# 2LCI2C.net
KiCad netlist of a schematic drawn in EAGLE
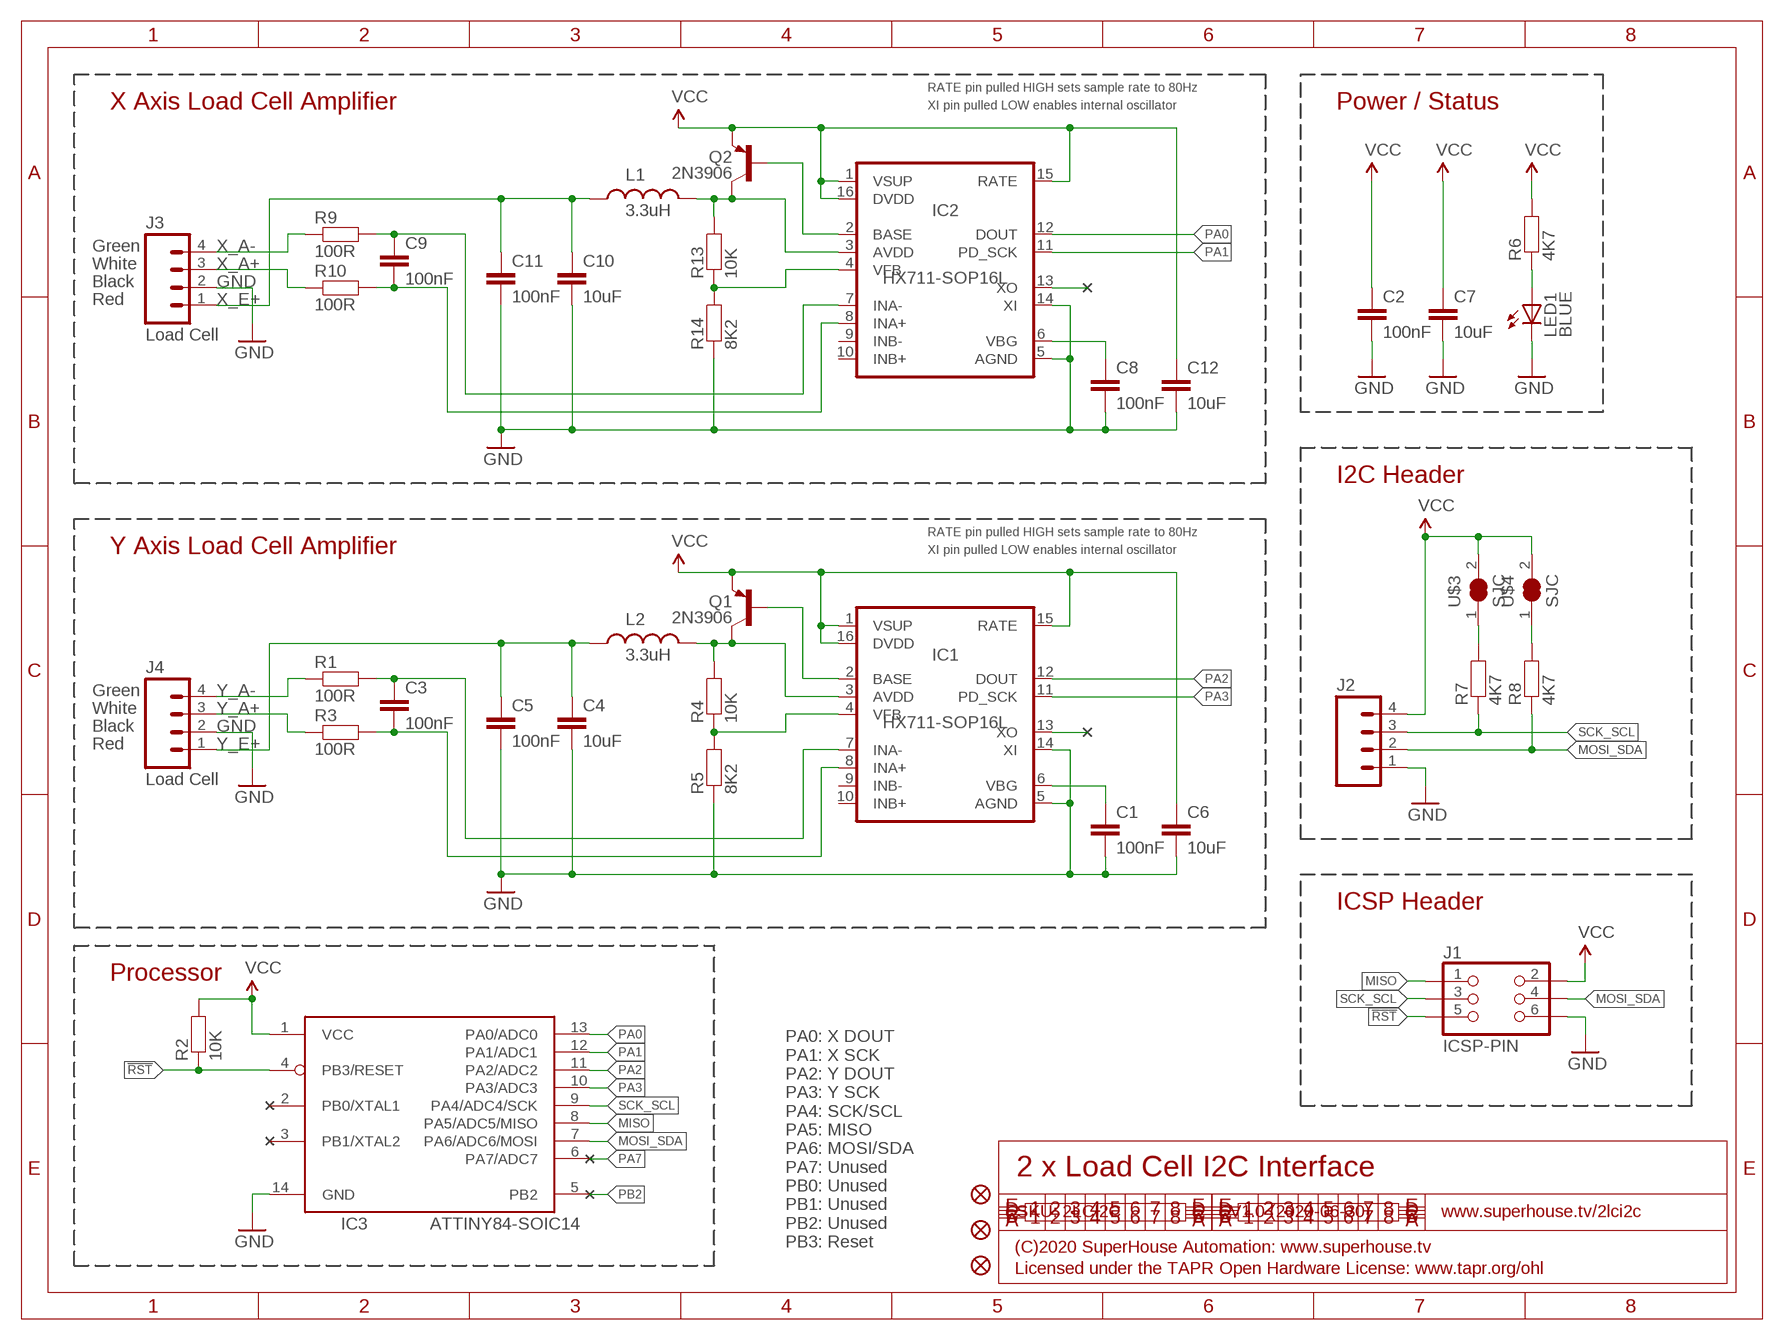
[diagram p0: schematic, sheet 1]

(export (version "E")
  (design (tool "Eeschema 10.0.6"))
  (components
    (comp (ref "C1")
      (value "100nF")
      (footprint "eagle-import:C0603")
      (libsource (lib "eagle-import") (part "CAP0603"))
    )
    (comp (ref "C2")
      (value "100nF")
      (footprint "eagle-import:C0603")
      (libsource (lib "eagle-import") (part "CAP0603"))
    )
    (comp (ref "C3")
      (value "100nF")
      (footprint "eagle-import:C0603")
      (libsource (lib "eagle-import") (part "CAP0603"))
    )
    (comp (ref "C4")
      (value "10uF")
      (footprint "eagle-import:C0805")
      (libsource (lib "eagle-import") (part "CAP0805"))
    )
    (comp (ref "C5")
      (value "100nF")
      (footprint "eagle-import:C0603")
      (libsource (lib "eagle-import") (part "CAP0603"))
    )
    (comp (ref "C6")
      (value "10uF")
      (footprint "eagle-import:C0805")
      (libsource (lib "eagle-import") (part "CAP0805"))
    )
    (comp (ref "C7")
      (value "10uF")
      (footprint "eagle-import:C0805")
      (libsource (lib "eagle-import") (part "CAP0805"))
    )
    (comp (ref "C8")
      (value "100nF")
      (footprint "eagle-import:C0603")
      (libsource (lib "eagle-import") (part "CAP0603"))
    )
    (comp (ref "C9")
      (value "100nF")
      (footprint "eagle-import:C0603")
      (libsource (lib "eagle-import") (part "CAP0603"))
    )
    (comp (ref "C10")
      (value "10uF")
      (footprint "eagle-import:C0805")
      (libsource (lib "eagle-import") (part "CAP0805"))
    )
    (comp (ref "C11")
      (value "100nF")
      (footprint "eagle-import:C0603")
      (libsource (lib "eagle-import") (part "CAP0603"))
    )
    (comp (ref "C12")
      (value "10uF")
      (footprint "eagle-import:C0805")
      (libsource (lib "eagle-import") (part "CAP0805"))
    )
    (comp (ref "IC1")
      (value "HX711-SOP16L")
      (footprint "eagle-import:SOP16-L")
      (libsource (lib "eagle-import") (part "HX711-SOP16L"))
    )
    (comp (ref "IC2")
      (value "HX711-SOP16L")
      (footprint "eagle-import:SOP16-L")
      (libsource (lib "eagle-import") (part "HX711-SOP16L"))
    )
    (comp (ref "IC3")
      (value "ATTINY84-SOIC14")
      (footprint "eagle-import:SOIC14")
      (libsource (lib "eagle-import") (part "ATTINY84-SOIC14"))
    )
    (comp (ref "J1")
      (value "ICSP-PIN")
      (footprint "eagle-import:2X03-ICSP")
      (libsource (lib "eagle-import") (part "ICSP-PIN"))
    )
    (comp (ref "J2")
      (value "M04-PLAIN")
      (footprint "eagle-import:1X04")
      (libsource (lib "eagle-import") (part "M04-PLAIN"))
    )
    (comp (ref "J3")
      (value "Load Cell")
      (footprint "eagle-import:1X04-1.27-PLAIN")
      (libsource (lib "eagle-import") (part "M04-1.27-PLAIN"))
    )
    (comp (ref "J4")
      (value "Load Cell")
      (footprint "eagle-import:1X04-1.27-PLAIN")
      (libsource (lib "eagle-import") (part "M04-1.27-PLAIN"))
    )
    (comp (ref "L1")
      (value "3.3uH")
      (footprint "eagle-import:L0603")
      (libsource (lib "eagle-import") (part "INDUCTOR0603"))
    )
    (comp (ref "L2")
      (value "3.3uH")
      (footprint "eagle-import:L0603")
      (libsource (lib "eagle-import") (part "INDUCTOR0603"))
    )
    (comp (ref "LED1")
      (value "BLUE")
      (footprint "eagle-import:LED-0603")
      (libsource (lib "eagle-import") (part "LED0603"))
    )
    (comp (ref "Q1")
      (value "2N3906")
      (footprint "eagle-import:SOT23-BEC")
      (libsource (lib "eagle-import") (part "TRANS_PNPSOT23-BECMMBT3906LT1"))
    )
    (comp (ref "Q2")
      (value "2N3906")
      (footprint "eagle-import:SOT23-BEC")
      (libsource (lib "eagle-import") (part "TRANS_PNPSOT23-BECMMBT3906LT1"))
    )
    (comp (ref "R1")
      (value "100R")
      (footprint "eagle-import:R0603")
      (libsource (lib "eagle-import") (part "RESISTOR0603"))
    )
    (comp (ref "R2")
      (value "10K")
      (footprint "eagle-import:R0603")
      (libsource (lib "eagle-import") (part "RESISTOR0603"))
    )
    (comp (ref "R3")
      (value "100R")
      (footprint "eagle-import:R0603")
      (libsource (lib "eagle-import") (part "RESISTOR0603"))
    )
    (comp (ref "R4")
      (value "10K")
      (footprint "eagle-import:R0603")
      (libsource (lib "eagle-import") (part "RESISTOR0603"))
    )
    (comp (ref "R5")
      (value "8K2")
      (footprint "eagle-import:R0603")
      (libsource (lib "eagle-import") (part "RESISTOR0603"))
    )
    (comp (ref "R6")
      (value "4K7")
      (footprint "eagle-import:R0603")
      (libsource (lib "eagle-import") (part "RESISTOR0603"))
    )
    (comp (ref "R7")
      (value "4K7")
      (footprint "eagle-import:R0603")
      (libsource (lib "eagle-import") (part "RESISTOR0603"))
    )
    (comp (ref "R8")
      (value "4K7")
      (footprint "eagle-import:R0603")
      (libsource (lib "eagle-import") (part "RESISTOR0603"))
    )
    (comp (ref "R9")
      (value "100R")
      (footprint "eagle-import:R0603")
      (libsource (lib "eagle-import") (part "RESISTOR0603"))
    )
    (comp (ref "R10")
      (value "100R")
      (footprint "eagle-import:R0603")
      (libsource (lib "eagle-import") (part "RESISTOR0603"))
    )
    (comp (ref "R13")
      (value "10K")
      (footprint "eagle-import:R0603")
      (libsource (lib "eagle-import") (part "RESISTOR0603"))
    )
    (comp (ref "R14")
      (value "8K2")
      (footprint "eagle-import:R0603")
      (libsource (lib "eagle-import") (part "RESISTOR0603"))
    )
    (comp (ref "U$3")
      (value "SJC")
      (footprint "eagle-import:SJC")
      (libsource (lib "eagle-import") (part "SJC-NORMAL"))
    )
    (comp (ref "U$4")
      (value "SJC")
      (footprint "eagle-import:SJC")
      (libsource (lib "eagle-import") (part "SJC-NORMAL"))
    )
    (comp (ref "U$5")
      (value "FIDUCIAL1X2.5")
      (footprint "eagle-import:FIDUCIAL-1X2.5")
      (libsource (lib "eagle-import") (part "FIDUCIAL1X2.5"))
    )
    (comp (ref "U$10")
      (value "FIDUCIAL1X2.5")
      (footprint "eagle-import:FIDUCIAL-1X2.5")
      (libsource (lib "eagle-import") (part "FIDUCIAL1X2.5"))
    )
    (comp (ref "U$11")
      (value "FIDUCIAL1X2.5")
      (footprint "eagle-import:FIDUCIAL-1X2.5")
      (libsource (lib "eagle-import") (part "FIDUCIAL1X2.5"))
    )
  )
  (nets
    (net (code "1") (name "/X_A+") (class "Default")
      (node (ref "J3") (pin "3") (pinfunction "3_3") (pintype "passive"))
      (node (ref "R10") (pin "1") (pinfunction "1_1") (pintype "passive"))
    )
    (net (code "2") (name "/X_A-") (class "Default")
      (node (ref "J3") (pin "4") (pinfunction "4_4") (pintype "passive"))
      (node (ref "R9") (pin "1") (pinfunction "1_1") (pintype "passive"))
    )
    (net (code "3") (name "/X_E+") (class "Default")
      (node (ref "C10") (pin "1") (pinfunction "1_1") (pintype "passive"))
      (node (ref "C11") (pin "1") (pinfunction "1_1") (pintype "passive"))
      (node (ref "J3") (pin "1") (pinfunction "1_1") (pintype "passive"))
      (node (ref "L1") (pin "1") (pinfunction "1_1") (pintype "passive"))
    )
    (net (code "4") (name "/Y_A+") (class "Default")
      (node (ref "J4") (pin "3") (pinfunction "3_3") (pintype "passive"))
      (node (ref "R3") (pin "1") (pinfunction "1_1") (pintype "passive"))
    )
    (net (code "5") (name "/Y_A-") (class "Default")
      (node (ref "J4") (pin "4") (pinfunction "4_4") (pintype "passive"))
      (node (ref "R1") (pin "1") (pinfunction "1_1") (pintype "passive"))
    )
    (net (code "6") (name "/Y_E+") (class "Default")
      (node (ref "C4") (pin "1") (pinfunction "1_1") (pintype "passive"))
      (node (ref "C5") (pin "1") (pinfunction "1_1") (pintype "passive"))
      (node (ref "J4") (pin "1") (pinfunction "1_1") (pintype "passive"))
      (node (ref "L2") (pin "1") (pinfunction "1_1") (pintype "passive"))
    )
    (net (code "7") (name "/~{RST}") (class "Default")
      (node (ref "IC3") (pin "4") (pinfunction "PB3/RESET_4") (pintype "bidirectional"))
      (node (ref "J1") (pin "5") (pinfunction "5_5") (pintype "passive"))
      (node (ref "R2") (pin "1") (pinfunction "1_1") (pintype "passive"))
    )
    (net (code "8") (name "GND") (class "Default")
      (node (ref "C1") (pin "2") (pinfunction "2_2") (pintype "passive"))
      (node (ref "C10") (pin "2") (pinfunction "2_2") (pintype "passive"))
      (node (ref "C11") (pin "2") (pinfunction "2_2") (pintype "passive"))
      (node (ref "C12") (pin "2") (pinfunction "2_2") (pintype "passive"))
      (node (ref "C2") (pin "2") (pinfunction "2_2") (pintype "passive"))
      (node (ref "C4") (pin "2") (pinfunction "2_2") (pintype "passive"))
      (node (ref "C5") (pin "2") (pinfunction "2_2") (pintype "passive"))
      (node (ref "C6") (pin "2") (pinfunction "2_2") (pintype "passive"))
      (node (ref "C7") (pin "2") (pinfunction "2_2") (pintype "passive"))
      (node (ref "C8") (pin "2") (pinfunction "2_2") (pintype "passive"))
      (node (ref "IC1") (pin "14") (pinfunction "XI_14") (pintype "power_in"))
      (node (ref "IC1") (pin "5") (pinfunction "AGND_5") (pintype "power_in"))
      (node (ref "IC2") (pin "14") (pinfunction "XI_14") (pintype "power_in"))
      (node (ref "IC2") (pin "5") (pinfunction "AGND_5") (pintype "power_in"))
      (node (ref "IC3") (pin "14") (pinfunction "GND_14") (pintype "bidirectional"))
      (node (ref "J1") (pin "6") (pinfunction "6_6") (pintype "passive"))
      (node (ref "J2") (pin "1") (pinfunction "1_1") (pintype "passive"))
      (node (ref "J3") (pin "2") (pinfunction "2_2") (pintype "passive"))
      (node (ref "J4") (pin "2") (pinfunction "2_2") (pintype "passive"))
      (node (ref "LED1") (pin "C") (pinfunction "C_C") (pintype "passive"))
      (node (ref "R14") (pin "1") (pinfunction "1_1") (pintype "passive"))
      (node (ref "R5") (pin "1") (pinfunction "1_1") (pintype "passive"))
    )
    (net (code "9") (name "MISO") (class "Default")
      (node (ref "IC3") (pin "8") (pinfunction "PA5/ADC5/MISO_8") (pintype "bidirectional"))
      (node (ref "J1") (pin "1") (pinfunction "1_1") (pintype "passive"))
    )
    (net (code "10") (name "MOSI_SDA") (class "Default")
      (node (ref "IC3") (pin "7") (pinfunction "PA6/ADC6/MOSI_7") (pintype "bidirectional"))
      (node (ref "J1") (pin "4") (pinfunction "4_4") (pintype "passive"))
      (node (ref "J2") (pin "2") (pinfunction "2_2") (pintype "passive"))
      (node (ref "R8") (pin "1") (pinfunction "1_1") (pintype "passive"))
    )
    (net (code "11") (name "Net-(IC1-AVDD)") (class "Default")
      (node (ref "IC1") (pin "3") (pinfunction "AVDD_3") (pintype "bidirectional"))
      (node (ref "L2") (pin "2") (pinfunction "2_2") (pintype "passive"))
      (node (ref "Q1") (pin "C") (pinfunction "C_C") (pintype "passive"))
      (node (ref "R4") (pin "2") (pinfunction "2_2") (pintype "passive"))
    )
    (net (code "12") (name "Net-(IC1-BASE)") (class "Default")
      (node (ref "IC1") (pin "2") (pinfunction "BASE_2") (pintype "bidirectional"))
      (node (ref "Q1") (pin "B") (pinfunction "B_B") (pintype "passive"))
    )
    (net (code "13") (name "Net-(IC1-INA+)") (class "Default")
      (node (ref "C3") (pin "2") (pinfunction "2_2") (pintype "passive"))
      (node (ref "IC1") (pin "8") (pinfunction "INA+_8") (pintype "bidirectional"))
      (node (ref "R3") (pin "2") (pinfunction "2_2") (pintype "passive"))
    )
    (net (code "14") (name "Net-(IC1-INA-)") (class "Default")
      (node (ref "C3") (pin "1") (pinfunction "1_1") (pintype "passive"))
      (node (ref "IC1") (pin "7") (pinfunction "INA-_7") (pintype "bidirectional"))
      (node (ref "R1") (pin "2") (pinfunction "2_2") (pintype "passive"))
    )
    (net (code "15") (name "Net-(IC1-VBG)") (class "Default")
      (node (ref "C1") (pin "1") (pinfunction "1_1") (pintype "passive"))
      (node (ref "IC1") (pin "6") (pinfunction "VBG_6") (pintype "input"))
    )
    (net (code "16") (name "Net-(IC1-VFB)") (class "Default")
      (node (ref "IC1") (pin "4") (pinfunction "VFB_4") (pintype "bidirectional"))
      (node (ref "R4") (pin "1") (pinfunction "1_1") (pintype "passive"))
      (node (ref "R5") (pin "2") (pinfunction "2_2") (pintype "passive"))
    )
    (net (code "17") (name "Net-(IC2-AVDD)") (class "Default")
      (node (ref "IC2") (pin "3") (pinfunction "AVDD_3") (pintype "bidirectional"))
      (node (ref "L1") (pin "2") (pinfunction "2_2") (pintype "passive"))
      (node (ref "Q2") (pin "C") (pinfunction "C_C") (pintype "passive"))
      (node (ref "R13") (pin "2") (pinfunction "2_2") (pintype "passive"))
    )
    (net (code "18") (name "Net-(IC2-BASE)") (class "Default")
      (node (ref "IC2") (pin "2") (pinfunction "BASE_2") (pintype "bidirectional"))
      (node (ref "Q2") (pin "B") (pinfunction "B_B") (pintype "passive"))
    )
    (net (code "19") (name "Net-(IC2-INA+)") (class "Default")
      (node (ref "C9") (pin "2") (pinfunction "2_2") (pintype "passive"))
      (node (ref "IC2") (pin "8") (pinfunction "INA+_8") (pintype "bidirectional"))
      (node (ref "R10") (pin "2") (pinfunction "2_2") (pintype "passive"))
    )
    (net (code "20") (name "Net-(IC2-INA-)") (class "Default")
      (node (ref "C9") (pin "1") (pinfunction "1_1") (pintype "passive"))
      (node (ref "IC2") (pin "7") (pinfunction "INA-_7") (pintype "bidirectional"))
      (node (ref "R9") (pin "2") (pinfunction "2_2") (pintype "passive"))
    )
    (net (code "21") (name "Net-(IC2-VBG)") (class "Default")
      (node (ref "C8") (pin "1") (pinfunction "1_1") (pintype "passive"))
      (node (ref "IC2") (pin "6") (pinfunction "VBG_6") (pintype "input"))
    )
    (net (code "22") (name "Net-(IC2-VFB)") (class "Default")
      (node (ref "IC2") (pin "4") (pinfunction "VFB_4") (pintype "bidirectional"))
      (node (ref "R13") (pin "1") (pinfunction "1_1") (pintype "passive"))
      (node (ref "R14") (pin "2") (pinfunction "2_2") (pintype "passive"))
    )
    (net (code "23") (name "Net-(LED1-PadA)") (class "Default")
      (node (ref "LED1") (pin "A") (pinfunction "A_A") (pintype "passive"))
      (node (ref "R6") (pin "1") (pinfunction "1_1") (pintype "passive"))
    )
    (net (code "24") (name "Net-(R7-Pad2)") (class "Default")
      (node (ref "R7") (pin "2") (pinfunction "2_2") (pintype "passive"))
      (node (ref "U$3") (pin "1") (pinfunction "1_1") (pintype "passive"))
    )
    (net (code "25") (name "Net-(R8-Pad2)") (class "Default")
      (node (ref "R8") (pin "2") (pinfunction "2_2") (pintype "passive"))
      (node (ref "U$4") (pin "1") (pinfunction "1_1") (pintype "passive"))
    )
    (net (code "26") (name "PA0") (class "Default")
      (node (ref "IC2") (pin "12") (pinfunction "DOUT_12") (pintype "bidirectional"))
      (node (ref "IC3") (pin "13") (pinfunction "PA0/ADC0_13") (pintype "bidirectional"))
    )
    (net (code "27") (name "PA1") (class "Default")
      (node (ref "IC2") (pin "11") (pinfunction "PD_SCK_11") (pintype "bidirectional"))
      (node (ref "IC3") (pin "12") (pinfunction "PA1/ADC1_12") (pintype "bidirectional"))
    )
    (net (code "28") (name "PA2") (class "Default")
      (node (ref "IC1") (pin "12") (pinfunction "DOUT_12") (pintype "bidirectional"))
      (node (ref "IC3") (pin "11") (pinfunction "PA2/ADC2_11") (pintype "bidirectional"))
    )
    (net (code "29") (name "PA3") (class "Default")
      (node (ref "IC1") (pin "11") (pinfunction "PD_SCK_11") (pintype "bidirectional"))
      (node (ref "IC3") (pin "10") (pinfunction "PA3/ADC3_10") (pintype "bidirectional"))
    )
    (net (code "30") (name "PA7") (class "Default")
      (node (ref "IC3") (pin "6") (pinfunction "PA7/ADC7_6") (pintype "bidirectional"))
    )
    (net (code "31") (name "PB2") (class "Default")
      (node (ref "IC3") (pin "5") (pinfunction "PB2_5") (pintype "bidirectional"))
    )
    (net (code "32") (name "SCK_SCL") (class "Default")
      (node (ref "IC3") (pin "9") (pinfunction "PA4/ADC4/SCK_9") (pintype "bidirectional"))
      (node (ref "J1") (pin "3") (pinfunction "3_3") (pintype "passive"))
      (node (ref "J2") (pin "3") (pinfunction "3_3") (pintype "passive"))
      (node (ref "R7") (pin "1") (pinfunction "1_1") (pintype "passive"))
    )
    (net (code "33") (name "VCC") (class "Default")
      (node (ref "C12") (pin "1") (pinfunction "1_1") (pintype "passive"))
      (node (ref "C2") (pin "1") (pinfunction "1_1") (pintype "passive"))
      (node (ref "C6") (pin "1") (pinfunction "1_1") (pintype "passive"))
      (node (ref "C7") (pin "1") (pinfunction "1_1") (pintype "passive"))
      (node (ref "IC1") (pin "1") (pinfunction "VSUP_1") (pintype "power_in"))
      (node (ref "IC1") (pin "15") (pinfunction "RATE_15") (pintype "input"))
      (node (ref "IC1") (pin "16") (pinfunction "DVDD_16") (pintype "input"))
      (node (ref "IC2") (pin "1") (pinfunction "VSUP_1") (pintype "power_in"))
      (node (ref "IC2") (pin "15") (pinfunction "RATE_15") (pintype "input"))
      (node (ref "IC2") (pin "16") (pinfunction "DVDD_16") (pintype "input"))
      (node (ref "IC3") (pin "1") (pinfunction "VCC_1") (pintype "bidirectional"))
      (node (ref "J1") (pin "2") (pinfunction "2_2") (pintype "passive"))
      (node (ref "J2") (pin "4") (pinfunction "4_4") (pintype "passive"))
      (node (ref "Q1") (pin "E") (pinfunction "E_E") (pintype "passive"))
      (node (ref "Q2") (pin "E") (pinfunction "E_E") (pintype "passive"))
      (node (ref "R2") (pin "2") (pinfunction "2_2") (pintype "passive"))
      (node (ref "R6") (pin "2") (pinfunction "2_2") (pintype "passive"))
      (node (ref "U$3") (pin "2") (pinfunction "2_2") (pintype "passive"))
      (node (ref "U$4") (pin "2") (pinfunction "2_2") (pintype "passive"))
    )
    (net (code "34") (name "unconnected-(IC1-INB+-Pad10)") (class "Default")
      (node (ref "IC1") (pin "10") (pinfunction "INB+_10") (pintype "bidirectional"))
    )
    (net (code "35") (name "unconnected-(IC1-INB--Pad9)") (class "Default")
      (node (ref "IC1") (pin "9") (pinfunction "INB-_9") (pintype "bidirectional"))
    )
    (net (code "36") (name "unconnected-(IC1-XO-Pad13)") (class "Default")
      (node (ref "IC1") (pin "13") (pinfunction "XO_13") (pintype "power_in"))
    )
    (net (code "37") (name "unconnected-(IC2-INB+-Pad10)") (class "Default")
      (node (ref "IC2") (pin "10") (pinfunction "INB+_10") (pintype "bidirectional"))
    )
    (net (code "38") (name "unconnected-(IC2-INB--Pad9)") (class "Default")
      (node (ref "IC2") (pin "9") (pinfunction "INB-_9") (pintype "bidirectional"))
    )
    (net (code "39") (name "unconnected-(IC2-XO-Pad13)") (class "Default")
      (node (ref "IC2") (pin "13") (pinfunction "XO_13") (pintype "power_in"))
    )
    (net (code "40") (name "unconnected-(IC3-PB0{slash}XTAL1-Pad2)") (class "Default")
      (node (ref "IC3") (pin "2") (pinfunction "PB0/XTAL1_2") (pintype "bidirectional"))
    )
    (net (code "41") (name "unconnected-(IC3-PB1{slash}XTAL2-Pad3)") (class "Default")
      (node (ref "IC3") (pin "3") (pinfunction "PB1/XTAL2_3") (pintype "bidirectional"))
    )
  )
)
